# DisplayConn.net
KiCad netlist of a schematic drawn in Altium Designer
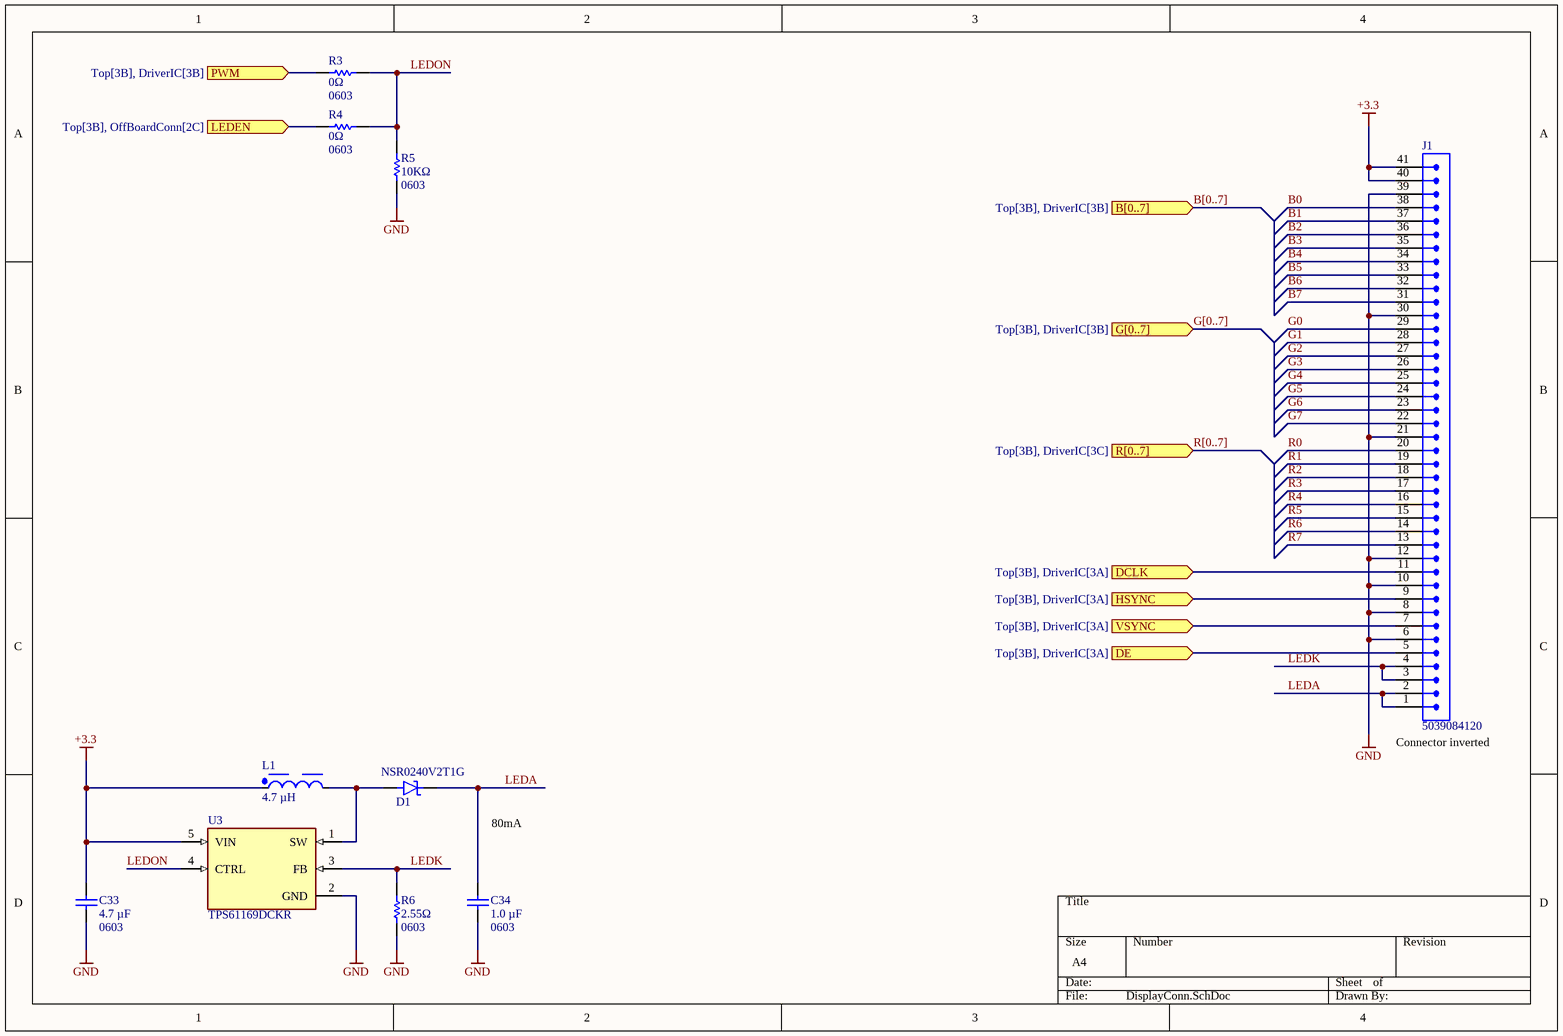
[diagram p0: DisplayConn.SchDoc]

(export (version "E")
  (design (tool "Eeschema 10.0.6"))
  (components
    (comp (ref "C33")
      (value "4.7 µF")
      (footprint "0603")
      (description "4.7 µF ±10% 35V Ceramic Capacitor X5R 0603 (1608 Metric)")
      (fields (field (name "CASE") "0603") (field (name "TOLERANCE") "±10%") (field (name "VOLTAGE") "35V"))
      (libsource (lib "Murata Electronics") (part "GRM188R6YA475KE15D"))
    )
    (comp (ref "C34")
      (value "1.0 µF")
      (footprint "0603")
      (description "1 µF ±10% 50V Ceramic Capacitor X7T 0603 (1608 Metric)")
      (fields (field (name "CASE") "0603") (field (name "TOLERANCE") "±10%") (field (name "VOLTAGE") "50V"))
      (libsource (lib "Murata Electronics") (part "GRM188D71H105KE01J"))
    )
    (comp (ref "D1")
      (value "NSR0240V2T1G")
      (footprint "SOD523")
      (description "Diode 40 V 250mA Surface Mount SOD-523")
      (libsource (lib "Onsemi") (part "NSR0240V2T1G"))
    )
    (comp (ref "J1")
      (value "5039084120")
      (footprint "41POS")
      (description "41 Position FFC Connector Contacts, Bottom 0.020\" (0.50mm) Surface Mount, Right Angle")
      (libsource (lib "Molex") (part "5039084120"))
    )
    (comp (ref "L1")
      (value "4.7 µH")
      (footprint "4.50mm x 4.00mm")
      (description "4.7 µH Unshielded Drum Core, Wirewound Inductor 1.82 A 110mOhm Max Nonstandard")
      (fields (field (name "Comment") "744773047"))
      (libsource (lib "Wurth Elektronik WE-HCI") (part "744773047"))
    )
    (comp (ref "R3")
      (value "0Ω")
      (footprint "0603")
      (description "0 Ohms Jumper Chip Resistor 0603 (1608 Metric) Automotive AEC-Q200 Thick Film")
      (fields
        (field (name "CASE") "0603")
        (field (name "TOLERANCE") "0")
        (field (name "Comment") "RMCF0603ZT0R00")
      )
      (libsource (lib "Stackpole Electronics Inc") (part "RMCF0603ZT0R00"))
    )
    (comp (ref "R4")
      (value "0Ω")
      (footprint "0603")
      (description "0 Ohms Jumper Chip Resistor 0603 (1608 Metric) Automotive AEC-Q200 Thick Film")
      (fields
        (field (name "CASE") "0603")
        (field (name "TOLERANCE") "0")
        (field (name "Comment") "RMCF0603ZT0R00")
      )
      (libsource (lib "Stackpole Electronics Inc") (part "RMCF0603ZT0R00"))
    )
    (comp (ref "R5")
      (value "10KΩ")
      (footprint "0603")
      (description "10 kOhms ±1% 0.1W, 1/10W Chip Resistor 0603 (1608 Metric) Automotive AEC-Q200 Thick Film")
      (fields (field (name "CASE") "0603") (field (name "TOLERANCE") "1%") (field (name "POWER") "0.1W"))
      (libsource (lib "Stackpole Electronics Inc") (part "RMCF0603FG10K0"))
    )
    (comp (ref "R6")
      (value "2.55Ω")
      (footprint "0603")
      (description "2.55 Ohms ±1% 0.1W, 1/10W Chip Resistor 0603 (1608 Metric) Automotive AEC-Q200 Thick Film")
      (fields (field (name "CASE") "0603") (field (name "TOLERANCE") "1%") (field (name "POWER") "0.1W"))
      (libsource (lib "Stackpole Electronics Inc") (part "RMCF0603FT2R55"))
    )
    (comp (ref "U3")
      (value "TPS61169DCKR")
      (footprint "SOT-353")
      (description "LED Driver IC 1 Output DC DC Regulator Step-Up (Boost) PWM Dimming 1.8A (Switch) SC-70-5")
      (libsource (lib "Texas Instruments") (part "TPS61169DCKR"))
    )
  )
  (nets
    (net (code "1") (name "+3.3") (class "Default")
      (node (ref "C33") (pin "2") (pinfunction "2_2") (pintype "passive"))
      (node (ref "J1") (pin "40") (pinfunction "40_40") (pintype "passive"))
      (node (ref "J1") (pin "41") (pinfunction "41_41") (pintype "passive"))
      (node (ref "L1") (pin "1") (pinfunction "1_1") (pintype "passive"))
      (node (ref "U3") (pin "5") (pinfunction "VIN_5") (pintype "input"))
    )
    (net (code "2") (name "/B0") (class "Default")
      (node (ref "J1") (pin "38") (pinfunction "38_38") (pintype "passive"))
    )
    (net (code "3") (name "/B1") (class "Default")
      (node (ref "J1") (pin "37") (pinfunction "37_37") (pintype "passive"))
    )
    (net (code "4") (name "/B2") (class "Default")
      (node (ref "J1") (pin "36") (pinfunction "36_36") (pintype "passive"))
    )
    (net (code "5") (name "/B3") (class "Default")
      (node (ref "J1") (pin "35") (pinfunction "35_35") (pintype "passive"))
    )
    (net (code "6") (name "/B4") (class "Default")
      (node (ref "J1") (pin "34") (pinfunction "34_34") (pintype "passive"))
    )
    (net (code "7") (name "/B5") (class "Default")
      (node (ref "J1") (pin "33") (pinfunction "33_33") (pintype "passive"))
    )
    (net (code "8") (name "/B6") (class "Default")
      (node (ref "J1") (pin "32") (pinfunction "32_32") (pintype "passive"))
    )
    (net (code "9") (name "/B7") (class "Default")
      (node (ref "J1") (pin "31") (pinfunction "31_31") (pintype "passive"))
    )
    (net (code "11") (name "/DCLK") (class "Default")
      (node (ref "J1") (pin "11") (pinfunction "11_11") (pintype "passive"))
    )
    (net (code "12") (name "/DE") (class "Default")
      (node (ref "J1") (pin "5") (pinfunction "5_5") (pintype "passive"))
    )
    (net (code "13") (name "/G0") (class "Default")
      (node (ref "J1") (pin "29") (pinfunction "29_29") (pintype "passive"))
    )
    (net (code "14") (name "/G1") (class "Default")
      (node (ref "J1") (pin "28") (pinfunction "28_28") (pintype "passive"))
    )
    (net (code "15") (name "/G2") (class "Default")
      (node (ref "J1") (pin "27") (pinfunction "27_27") (pintype "passive"))
    )
    (net (code "16") (name "/G3") (class "Default")
      (node (ref "J1") (pin "26") (pinfunction "26_26") (pintype "passive"))
    )
    (net (code "17") (name "/G4") (class "Default")
      (node (ref "J1") (pin "25") (pinfunction "25_25") (pintype "passive"))
    )
    (net (code "18") (name "/G5") (class "Default")
      (node (ref "J1") (pin "24") (pinfunction "24_24") (pintype "passive"))
    )
    (net (code "19") (name "/G6") (class "Default")
      (node (ref "J1") (pin "23") (pinfunction "23_23") (pintype "passive"))
    )
    (net (code "20") (name "/G7") (class "Default")
      (node (ref "J1") (pin "22") (pinfunction "22_22") (pintype "passive"))
    )
    (net (code "22") (name "/HSYNC") (class "Default")
      (node (ref "J1") (pin "9") (pinfunction "9_9") (pintype "passive"))
    )
    (net (code "23") (name "/LEDA") (class "Default")
      (node (ref "C34") (pin "2") (pinfunction "2_2") (pintype "passive"))
      (node (ref "D1") (pin "1") (pinfunction "C_1") (pintype "passive"))
      (node (ref "J1") (pin "1") (pinfunction "1_1") (pintype "passive"))
      (node (ref "J1") (pin "2") (pinfunction "2_2") (pintype "passive"))
    )
    (net (code "24") (name "/LEDEN") (class "Default")
      (node (ref "R4") (pin "2") (pinfunction "2_2") (pintype "passive"))
    )
    (net (code "25") (name "/LEDK") (class "Default")
      (node (ref "J1") (pin "3") (pinfunction "3_3") (pintype "passive"))
      (node (ref "J1") (pin "4") (pinfunction "4_4") (pintype "passive"))
      (node (ref "R6") (pin "1") (pinfunction "1_1") (pintype "passive"))
      (node (ref "U3") (pin "3") (pinfunction "FB_3") (pintype "input"))
    )
    (net (code "26") (name "/LEDON") (class "Default")
      (node (ref "R3") (pin "1") (pinfunction "1_1") (pintype "passive"))
      (node (ref "R4") (pin "1") (pinfunction "1_1") (pintype "passive"))
      (node (ref "R5") (pin "1") (pinfunction "1_1") (pintype "passive"))
      (node (ref "U3") (pin "4") (pinfunction "CTRL_4") (pintype "input"))
    )
    (net (code "27") (name "/PWM") (class "Default")
      (node (ref "R3") (pin "2") (pinfunction "2_2") (pintype "passive"))
    )
    (net (code "28") (name "/R0") (class "Default")
      (node (ref "J1") (pin "20") (pinfunction "20_20") (pintype "passive"))
    )
    (net (code "29") (name "/R1") (class "Default")
      (node (ref "J1") (pin "19") (pinfunction "19_19") (pintype "passive"))
    )
    (net (code "30") (name "/R2") (class "Default")
      (node (ref "J1") (pin "18") (pinfunction "18_18") (pintype "passive"))
    )
    (net (code "31") (name "/R3") (class "Default")
      (node (ref "J1") (pin "17") (pinfunction "17_17") (pintype "passive"))
    )
    (net (code "32") (name "/R4") (class "Default")
      (node (ref "J1") (pin "16") (pinfunction "16_16") (pintype "passive"))
    )
    (net (code "33") (name "/R5") (class "Default")
      (node (ref "J1") (pin "15") (pinfunction "15_15") (pintype "passive"))
    )
    (net (code "34") (name "/R6") (class "Default")
      (node (ref "J1") (pin "14") (pinfunction "14_14") (pintype "passive"))
    )
    (net (code "35") (name "/R7") (class "Default")
      (node (ref "J1") (pin "13") (pinfunction "13_13") (pintype "passive"))
    )
    (net (code "37") (name "/VSYNC") (class "Default")
      (node (ref "J1") (pin "7") (pinfunction "7_7") (pintype "passive"))
    )
    (net (code "38") (name "GND") (class "Default")
      (node (ref "C33") (pin "1") (pinfunction "1_1") (pintype "passive"))
      (node (ref "C34") (pin "1") (pinfunction "1_1") (pintype "passive"))
      (node (ref "J1") (pin "10") (pinfunction "10_10") (pintype "passive"))
      (node (ref "J1") (pin "12") (pinfunction "12_12") (pintype "passive"))
      (node (ref "J1") (pin "21") (pinfunction "21_21") (pintype "passive"))
      (node (ref "J1") (pin "30") (pinfunction "30_30") (pintype "passive"))
      (node (ref "J1") (pin "39") (pinfunction "39_39") (pintype "passive"))
      (node (ref "J1") (pin "6") (pinfunction "6_6") (pintype "passive"))
      (node (ref "J1") (pin "8") (pinfunction "8_8") (pintype "passive"))
      (node (ref "R5") (pin "2") (pinfunction "2_2") (pintype "passive"))
      (node (ref "R6") (pin "2") (pinfunction "2_2") (pintype "passive"))
      (node (ref "U3") (pin "2") (pinfunction "GND_2") (pintype "power_in"))
    )
    (net (code "39") (name "Net-(D1-A)") (class "Default")
      (node (ref "D1") (pin "2") (pinfunction "A_2") (pintype "passive"))
      (node (ref "L1") (pin "2") (pinfunction "2_2") (pintype "passive"))
      (node (ref "U3") (pin "1") (pinfunction "SW_1") (pintype "input"))
    )
  )
)
